# nguyenly.net
KiCad netlist of a schematic drawn in Altium Designer
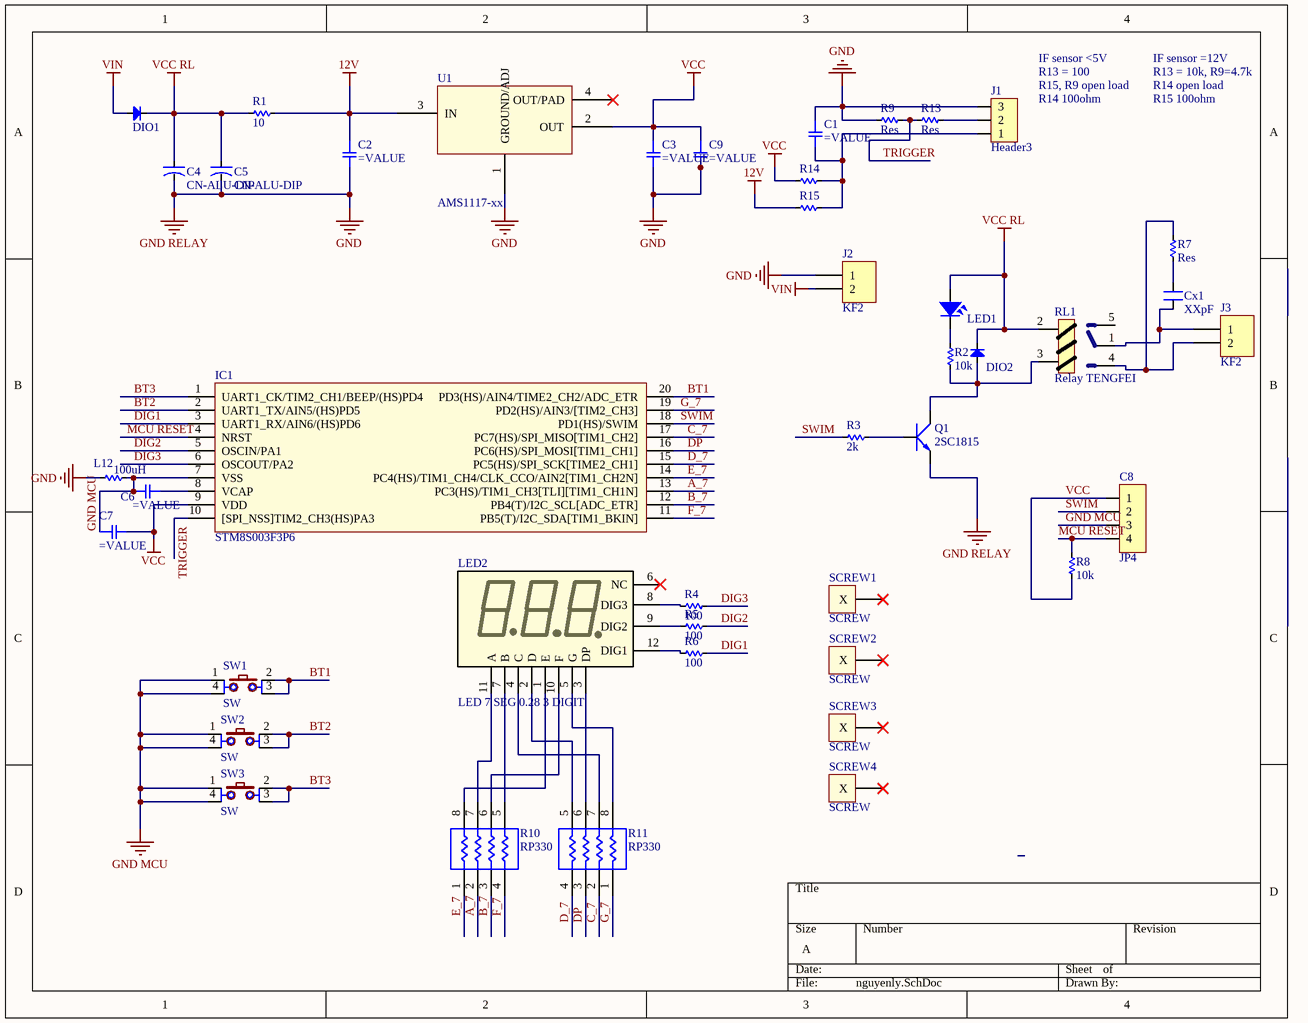
[diagram p0: nguyenly.SchDoc]

(export (version "E")
  (design (tool "Eeschema 10.0.6"))
  (components
    (comp (ref "C1")
      (value "~")
      (footprint "SMD-0805C")
      (description "CAP MLCC SMT")
      (libsource (lib "HOANG_ANH") (part "CAPACITOR"))
    )
    (comp (ref "C2")
      (value "~")
      (footprint "SMD-0805C")
      (description "CAP MLCC SMT")
      (libsource (lib "HOANG_ANH") (part "CAPACITOR"))
    )
    (comp (ref "C3")
      (value "~")
      (footprint "SMD-0805C")
      (description "CAP MLCC SMT")
      (libsource (lib "HOANG_ANH") (part "CAPACITOR"))
    )
    (comp (ref "C4")
      (value "CN-ALU-DIP")
      (footprint "CA-ALU-8")
      (description "Capacitor (Semiconductor SIM Model)")
      (fields (field (name "PUBLISHER") "Altium Limited"))
      (libsource (lib "LIBRARY") (part "CN-ALU-DIP"))
    )
    (comp (ref "C5")
      (value "CN-ALU-DIP")
      (footprint "CA-ALU-8")
      (description "Capacitor (Semiconductor SIM Model)")
      (fields (field (name "PUBLISHER") "Altium Limited"))
      (libsource (lib "LIBRARY") (part "CN-ALU-DIP"))
    )
    (comp (ref "C6")
      (value "~")
      (footprint "SMD-0805C")
      (description "CAP MLCC SMT")
      (libsource (lib "HOANG_ANH") (part "CAPACITOR"))
    )
    (comp (ref "C7")
      (value "~")
      (footprint "SMD-0805C")
      (description "CAP MLCC SMT")
      (libsource (lib "HOANG_ANH") (part "CAPACITOR"))
    )
    (comp (ref "C8")
      (value "JP4")
      (footprint "JP4-C1T")
      (description "WR-PHD 2.54 mm Angled Socket Header")
      (fields
        (field (name "MANUFACTURER") "Würth Elektronik eiSos GmbH")
        (field (name "PARTNO") "613004143121")
        (field (name "CREATED BY") "Karrer Zheng")
      )
      (libsource (lib "LIBRARY") (part "JP4"))
    )
    (comp (ref "C9")
      (value "~")
      (footprint "SMD-0805C")
      (description "CAP MLCC SMT")
      (libsource (lib "HOANG_ANH") (part "CAPACITOR"))
    )
    (comp (ref "Cx1") (value "XXpF") (footprint "CN2.5") (libsource (lib "LIBRARY") (part "CN")))
    (comp (ref "DIO1")
      (value "Diode SMD")
      (footprint "DIO-SMD-106")
      (description "Default Diode")
      (fields (field (name "PUBLISHER") "Altium Limited"))
      (libsource (lib "LIBRARY") (part "Diode SMD"))
    )
    (comp (ref "DIO2")
      (value "Diode SMD")
      (footprint "DIO-SMD-106")
      (description "Default Diode")
      (fields (field (name "PUBLISHER") "Altium Limited"))
      (libsource (lib "LIBRARY") (part "Diode SMD"))
    )
    (comp (ref "IC1")
      (value "STM8S003F3P6")
      (footprint "TSSOP20")
      (description "MCU 8BIT  8KB FLASH TSSOP-20")
      (fields (field (name "COPYRIGHT BY") "VanDungEvn"))
      (libsource (lib "LIBRARY") (part "STM8S003F3P6"))
    )
    (comp (ref "J1")
      (value "Header3")
      (footprint "Header3")
      (description "Header IDC, 3 x 1 Pin Vertical 2.54mm Pitch (Non-Boxed, Male)")
      (fields
        (field (name "MANUFACTURER") "Würth Elektronik eiSos GmbH")
        (field (name "PARTNO") "613002143121")
        (field (name "CREATED BY") "Karrer Zheng")
      )
      (libsource (lib "LIBRARY") (part "Header3"))
    )
    (comp (ref "J2")
      (value "KF2")
      (footprint "KF2-5.08")
      (fields
        (field (name "MANUFACTURER") "Würth Elektronik eiSos GmbH")
        (field (name "PARTNO") "691103110002")
        (field (name "CREATED BY") "Karrer Zheng")
      )
      (libsource (lib "LIBRARY") (part "KF2"))
    )
    (comp (ref "J3")
      (value "KF2")
      (footprint "KF2-5.08")
      (fields
        (field (name "MANUFACTURER") "Würth Elektronik eiSos GmbH")
        (field (name "PARTNO") "691103110002")
        (field (name "CREATED BY") "Karrer Zheng")
      )
      (libsource (lib "LIBRARY") (part "KF2"))
    )
    (comp (ref "L12")
      (value "100uH")
      (footprint "RES-SMD-0805")
      (description "Resistor")
      (fields
        (field (name "MANUFACTURER") "Generic Components")
        (field (name "PUBLISHER") "Altium Hobart Technology Centre")
      )
      (libsource (lib "LIBRARY") (part "Res-SMD"))
    )
    (comp (ref "LED1")
      (value "LED")
      (footprint "LED-0805-Yellow")
      (libsource (lib "LIBRARY") (part "LED SMD"))
    )
    (comp (ref "LED2")
      (value "LED 7 SEG 0.28 3 DIGIT")
      (footprint "LED 7 Seg 0.28, 3 digit, RED")
      (libsource (lib "HOANG_ANH") (part "LED 7 Segment"))
    )
    (comp (ref "Q1")
      (value "2SC1815")
      (footprint "TO92-123")
      (description "NPN 600mW, ECB")
      (libsource (lib "LIBRARY") (part "2SC1815"))
    )
    (comp (ref "R1")
      (value "10")
      (footprint "RES-SMD-0805")
      (description "Resistor")
      (fields
        (field (name "MANUFACTURER") "Generic Components")
        (field (name "PUBLISHER") "Altium Hobart Technology Centre")
      )
      (libsource (lib "LIBRARY") (part "Res-SMD"))
    )
    (comp (ref "R2")
      (value "10k")
      (footprint "RES-SMD-0805")
      (description "Resistor")
      (fields
        (field (name "MANUFACTURER") "Generic Components")
        (field (name "PUBLISHER") "Altium Hobart Technology Centre")
      )
      (libsource (lib "LIBRARY") (part "Res-SMD"))
    )
    (comp (ref "R3")
      (value "2k")
      (footprint "RES-SMD-0805")
      (description "Resistor")
      (fields
        (field (name "MANUFACTURER") "Generic Components")
        (field (name "PUBLISHER") "Altium Hobart Technology Centre")
      )
      (libsource (lib "LIBRARY") (part "Res-SMD"))
    )
    (comp (ref "R4")
      (value "100")
      (footprint "RES-SMD-0805")
      (description "Resistor")
      (fields
        (field (name "MANUFACTURER") "Generic Components")
        (field (name "PUBLISHER") "Altium Hobart Technology Centre")
      )
      (libsource (lib "LIBRARY") (part "Res-SMD"))
    )
    (comp (ref "R5")
      (value "100")
      (footprint "RES-SMD-0805")
      (description "Resistor")
      (fields
        (field (name "MANUFACTURER") "Generic Components")
        (field (name "PUBLISHER") "Altium Hobart Technology Centre")
      )
      (libsource (lib "LIBRARY") (part "Res-SMD"))
    )
    (comp (ref "R6")
      (value "100")
      (footprint "RES-SMD-0805")
      (description "Resistor")
      (fields
        (field (name "MANUFACTURER") "Generic Components")
        (field (name "PUBLISHER") "Altium Hobart Technology Centre")
      )
      (libsource (lib "LIBRARY") (part "Res-SMD"))
    )
    (comp (ref "R7")
      (value "Res")
      (footprint "RES-SMD-0805")
      (description "Resistor")
      (fields
        (field (name "MANUFACTURER") "Generic Components")
        (field (name "PUBLISHER") "Altium Hobart Technology Centre")
      )
      (libsource (lib "LIBRARY") (part "Res-SMD"))
    )
    (comp (ref "R8")
      (value "10k")
      (footprint "RES-SMD-0805")
      (description "Resistor")
      (fields
        (field (name "MANUFACTURER") "Generic Components")
        (field (name "PUBLISHER") "Altium Hobart Technology Centre")
      )
      (libsource (lib "LIBRARY") (part "Res-SMD"))
    )
    (comp (ref "R9")
      (value "Res")
      (footprint "RES-SMD-0805")
      (description "Resistor")
      (fields
        (field (name "MANUFACTURER") "Generic Components")
        (field (name "PUBLISHER") "Altium Hobart Technology Centre")
      )
      (libsource (lib "LIBRARY") (part "Res-SMD"))
    )
    (comp (ref "R10") (value "RP330") (footprint "RN4-0805") (libsource (lib "LIBRARY") (part "RN4-Dual")))
    (comp (ref "R11") (value "RP330") (footprint "RN4-0805") (libsource (lib "LIBRARY") (part "RN4-Dual")))
    (comp (ref "R13")
      (value "Res")
      (footprint "RES-SMD-0805")
      (description "Resistor")
      (fields
        (field (name "MANUFACTURER") "Generic Components")
        (field (name "PUBLISHER") "Altium Hobart Technology Centre")
      )
      (libsource (lib "LIBRARY") (part "Res-SMD"))
    )
    (comp (ref "R14")
      (value "Res")
      (footprint "RES-SMD-0805")
      (description "Resistor")
      (fields
        (field (name "MANUFACTURER") "Generic Components")
        (field (name "PUBLISHER") "Altium Hobart Technology Centre")
      )
      (libsource (lib "LIBRARY") (part "Res-SMD"))
    )
    (comp (ref "R15")
      (value "Res")
      (footprint "RES-SMD-0805")
      (description "Resistor")
      (fields
        (field (name "MANUFACTURER") "Generic Components")
        (field (name "PUBLISHER") "Altium Hobart Technology Centre")
      )
      (libsource (lib "LIBRARY") (part "Res-SMD"))
    )
    (comp (ref "RL1")
      (value "Relay TENGFEI")
      (footprint "JQC-T78-DC12V-A")
      (libsource (lib "HOANG_ANH") (part "Relay TENGFEI"))
    )
    (comp (ref "SCREW1") (value "SCREW") (footprint "SCREW-M5") (libsource (lib "HOANG_ANH") (part "SCREW")))
    (comp (ref "SCREW2") (value "SCREW") (footprint "SCREW-M5") (libsource (lib "HOANG_ANH") (part "SCREW")))
    (comp (ref "SCREW3") (value "SCREW") (footprint "SCREW-M5") (libsource (lib "HOANG_ANH") (part "SCREW")))
    (comp (ref "SCREW4") (value "SCREW") (footprint "SCREW-M5") (libsource (lib "HOANG_ANH") (part "SCREW")))
    (comp (ref "SW1")
      (value "SW")
      (footprint "SW2-DIP")
      (description "Switch button 4 pin")
      (libsource (lib "LIBRARY") (part "SW4"))
    )
    (comp (ref "SW2")
      (value "SW")
      (footprint "SW2-DIP")
      (description "Switch button 4 pin")
      (libsource (lib "LIBRARY") (part "SW4"))
    )
    (comp (ref "SW3")
      (value "SW")
      (footprint "SW2-DIP")
      (description "Switch button 4 pin")
      (libsource (lib "LIBRARY") (part "SW4"))
    )
    (comp (ref "U1")
      (value "AMS1117-xx")
      (footprint "SOT-233")
      (libsource (lib "HOANG_ANH") (part "AMS1117-xx"))
    )
  )
  (nets
    (net (code "1") (name "/A_7") (class "Default")
      (node (ref "IC1") (pin "13") (pinfunction "PC3(HS)/TIM1_CH3[TLI][TIM1_CH1N]_13") (pintype "passive"))
      (node (ref "R10") (pin "2") (pinfunction "2_2") (pintype "passive"))
    )
    (net (code "2") (name "/BT1") (class "Default")
      (node (ref "IC1") (pin "20") (pinfunction "PD3(HS)/AIN4/TIME2_CH2/ADC_ETR_20") (pintype "passive"))
      (node (ref "SW1") (pin "2") (pinfunction "2_2") (pintype "passive"))
      (node (ref "SW1") (pin "3") (pinfunction "3_3") (pintype "passive"))
    )
    (net (code "3") (name "/BT2") (class "Default")
      (node (ref "IC1") (pin "2") (pinfunction "UART1_TX/AIN5/(HS)PD5_2") (pintype "passive"))
      (node (ref "SW2") (pin "2") (pinfunction "2_2") (pintype "passive"))
      (node (ref "SW2") (pin "3") (pinfunction "3_3") (pintype "passive"))
    )
    (net (code "4") (name "/BT3") (class "Default")
      (node (ref "IC1") (pin "1") (pinfunction "UART1_CK/TIM2_CH1/BEEP/(HS)PD4_1") (pintype "passive"))
      (node (ref "SW3") (pin "2") (pinfunction "2_2") (pintype "passive"))
      (node (ref "SW3") (pin "3") (pinfunction "3_3") (pintype "passive"))
    )
    (net (code "5") (name "/B_7") (class "Default")
      (node (ref "IC1") (pin "12") (pinfunction "PB4(T)/I2C_SCL[ADC_ETR]_12") (pintype "passive"))
      (node (ref "R10") (pin "3") (pinfunction "3_3") (pintype "passive"))
    )
    (net (code "6") (name "/C_7") (class "Default")
      (node (ref "IC1") (pin "17") (pinfunction "PC7(HS)/SPI_MISO[TIM1_CH2]_17") (pintype "passive"))
      (node (ref "R11") (pin "2") (pinfunction "2_2") (pintype "passive"))
    )
    (net (code "7") (name "/DIG1") (class "Default")
      (node (ref "IC1") (pin "3") (pinfunction "UART1_RX/AIN6/(HS)PD6_3") (pintype "passive"))
      (node (ref "R6") (pin "1") (pinfunction "1_1") (pintype "passive"))
    )
    (net (code "8") (name "/DIG2") (class "Default")
      (node (ref "IC1") (pin "5") (pinfunction "OSCIN/PA1_5") (pintype "passive"))
      (node (ref "R5") (pin "1") (pinfunction "1_1") (pintype "passive"))
    )
    (net (code "9") (name "/DIG3") (class "Default")
      (node (ref "IC1") (pin "6") (pinfunction "OSCOUT/PA2_6") (pintype "passive"))
      (node (ref "R4") (pin "1") (pinfunction "1_1") (pintype "passive"))
    )
    (net (code "10") (name "/DP") (class "Default")
      (node (ref "IC1") (pin "16") (pinfunction "PC6(HS)/SPI_MOSI[TIM1_CH1]_16") (pintype "passive"))
      (node (ref "R11") (pin "3") (pinfunction "3_3") (pintype "passive"))
    )
    (net (code "11") (name "/D_7") (class "Default")
      (node (ref "IC1") (pin "15") (pinfunction "PC5(HS)/SPI_SCK[TIME2_CH1]_15") (pintype "passive"))
      (node (ref "R11") (pin "4") (pinfunction "4_4") (pintype "passive"))
    )
    (net (code "12") (name "/E_7") (class "Default")
      (node (ref "IC1") (pin "14") (pinfunction "PC4(HS)/TIM1_CH4/CLK_CCO/AIN2[TIM1_CH2N]_14") (pintype "passive"))
      (node (ref "R10") (pin "1") (pinfunction "1_1") (pintype "passive"))
    )
    (net (code "13") (name "/F_7") (class "Default")
      (node (ref "IC1") (pin "11") (pinfunction "PB5(T)/I2C_SDA[TIM1_BKIN]_11") (pintype "passive"))
      (node (ref "R10") (pin "4") (pinfunction "4_4") (pintype "passive"))
    )
    (net (code "14") (name "/G_7") (class "Default")
      (node (ref "IC1") (pin "19") (pinfunction "PD2(HS)/AIN3/[TIM2_CH3]_19") (pintype "passive"))
      (node (ref "R11") (pin "1") (pinfunction "1_1") (pintype "passive"))
    )
    (net (code "15") (name "/MCU RESET") (class "Default")
      (node (ref "C8") (pin "4") (pinfunction "4_4") (pintype "passive"))
      (node (ref "IC1") (pin "4") (pinfunction "NRST_4") (pintype "passive"))
      (node (ref "R8") (pin "2") (pinfunction "2_2") (pintype "passive"))
    )
    (net (code "16") (name "/SWIM") (class "Default")
      (node (ref "C8") (pin "2") (pinfunction "2_2") (pintype "passive"))
      (node (ref "IC1") (pin "18") (pinfunction "PD1(HS)/SWIM_18") (pintype "passive"))
      (node (ref "R3") (pin "2") (pinfunction "2_2") (pintype "passive"))
    )
    (net (code "17") (name "/TRIGGER") (class "Default")
      (node (ref "IC1") (pin "10") (pinfunction "[SPI_NSS]TIM2_CH3(HS)PA3_10") (pintype "passive"))
      (node (ref "R13") (pin "2") (pinfunction "2_2") (pintype "passive"))
      (node (ref "R9") (pin "1") (pinfunction "1_1") (pintype "passive"))
    )
    (net (code "18") (name "12V") (class "Default")
      (node (ref "C2") (pin "1") (pinfunction "1_1") (pintype "passive"))
      (node (ref "R1") (pin "1") (pinfunction "1_1") (pintype "passive"))
      (node (ref "R15") (pin "2") (pinfunction "2_2") (pintype "passive"))
      (node (ref "U1") (pin "3") (pinfunction "IN_3") (pintype "power_in"))
    )
    (net (code "19") (name "GND") (class "Default")
      (node (ref "C1") (pin "1") (pinfunction "1_1") (pintype "passive"))
      (node (ref "C2") (pin "2") (pinfunction "2_2") (pintype "passive"))
      (node (ref "C3") (pin "2") (pinfunction "2_2") (pintype "passive"))
      (node (ref "C4") (pin "2") (pinfunction "2_2") (pintype "passive"))
      (node (ref "C5") (pin "2") (pinfunction "2_2") (pintype "passive"))
      (node (ref "C9") (pin "2") (pinfunction "2_2") (pintype "passive"))
      (node (ref "J1") (pin "3") (pinfunction "3_3") (pintype "passive"))
      (node (ref "J2") (pin "1") (pinfunction "1_1") (pintype "passive"))
      (node (ref "L12") (pin "2") (pinfunction "2_2") (pintype "passive"))
      (node (ref "Q1") (pin "1") (pinfunction "E_1") (pintype "passive"))
      (node (ref "R9") (pin "2") (pinfunction "2_2") (pintype "passive"))
      (node (ref "U1") (pin "1") (pinfunction "GROUND/ADJ_1") (pintype "power_in"))
    )
    (net (code "20") (name "GND MCU") (class "Default")
      (node (ref "C6") (pin "1") (pinfunction "1_1") (pintype "passive"))
      (node (ref "C7") (pin "1") (pinfunction "1_1") (pintype "passive"))
      (node (ref "C8") (pin "3") (pinfunction "3_3") (pintype "passive"))
      (node (ref "IC1") (pin "7") (pinfunction "VSS_7") (pintype "passive"))
      (node (ref "L12") (pin "1") (pinfunction "1_1") (pintype "passive"))
      (node (ref "SW1") (pin "1") (pintype "passive"))
      (node (ref "SW1") (pin "4") (pinfunction "4_4") (pintype "passive"))
      (node (ref "SW2") (pin "1") (pintype "passive"))
      (node (ref "SW2") (pin "4") (pinfunction "4_4") (pintype "passive"))
      (node (ref "SW3") (pin "1") (pintype "passive"))
      (node (ref "SW3") (pin "4") (pinfunction "4_4") (pintype "passive"))
    )
    (net (code "21") (name "Net-(C1-Pad2)") (class "Default")
      (node (ref "C1") (pin "2") (pinfunction "2_2") (pintype "passive"))
      (node (ref "J1") (pin "1") (pinfunction "1_1") (pintype "passive"))
      (node (ref "R14") (pin "1") (pinfunction "1_1") (pintype "passive"))
      (node (ref "R15") (pin "1") (pinfunction "1_1") (pintype "passive"))
    )
    (net (code "22") (name "Net-(Cx1-Pad1)") (class "Default")
      (node (ref "Cx1") (pin "1") (pinfunction "1_1") (pintype "passive"))
      (node (ref "R7") (pin "2") (pinfunction "2_2") (pintype "passive"))
    )
    (net (code "23") (name "Net-(Cx1-Pad2)") (class "Default")
      (node (ref "Cx1") (pin "2") (pinfunction "2_2") (pintype "passive"))
      (node (ref "J3") (pin "1") (pinfunction "1_1") (pintype "passive"))
      (node (ref "RL1") (pin "1") (pinfunction "1_1") (pintype "passive"))
    )
    (net (code "24") (name "Net-(DIO2-A)") (class "Default")
      (node (ref "DIO2") (pin "1") (pinfunction "A_1") (pintype "passive"))
      (node (ref "Q1") (pin "2") (pinfunction "C_2") (pintype "passive"))
      (node (ref "R2") (pin "2") (pinfunction "2_2") (pintype "passive"))
      (node (ref "RL1") (pin "3") (pinfunction "3_3") (pintype "passive"))
    )
    (net (code "25") (name "Net-(IC1-VCAP)") (class "Default")
      (node (ref "C6") (pin "2") (pinfunction "2_2") (pintype "passive"))
      (node (ref "IC1") (pin "8") (pinfunction "VCAP_8") (pintype "passive"))
    )
    (net (code "26") (name "Net-(J1-Pad2)") (class "Default")
      (node (ref "J1") (pin "2") (pinfunction "2_2") (pintype "passive"))
      (node (ref "R13") (pin "1") (pinfunction "1_1") (pintype "passive"))
    )
    (net (code "27") (name "Net-(J3-Pad2)") (class "Default")
      (node (ref "J3") (pin "2") (pinfunction "2_2") (pintype "passive"))
      (node (ref "R7") (pin "1") (pinfunction "1_1") (pintype "passive"))
      (node (ref "RL1") (pin "4") (pinfunction "4_4") (pintype "passive"))
    )
    (net (code "28") (name "Net-(LED1-Pad2)") (class "Default")
      (node (ref "LED1") (pin "2") (pinfunction "2_2") (pintype "passive"))
      (node (ref "R2") (pin "1") (pinfunction "1_1") (pintype "passive"))
    )
    (net (code "29") (name "Net-(LED2-A)") (class "Default")
      (node (ref "LED2") (pin "11") (pinfunction "A_11") (pintype "passive"))
      (node (ref "R10") (pin "7") (pinfunction "7_7") (pintype "passive"))
    )
    (net (code "30") (name "Net-(LED2-B)") (class "Default")
      (node (ref "LED2") (pin "7") (pinfunction "B_7") (pintype "passive"))
      (node (ref "R10") (pin "5") (pinfunction "5_5") (pintype "passive"))
    )
    (net (code "31") (name "Net-(LED2-C)") (class "Default")
      (node (ref "LED2") (pin "4") (pinfunction "C_4") (pintype "passive"))
      (node (ref "R11") (pin "7") (pinfunction "7_7") (pintype "passive"))
    )
    (net (code "32") (name "Net-(LED2-D)") (class "Default")
      (node (ref "LED2") (pin "2") (pinfunction "D_2") (pintype "passive"))
      (node (ref "R11") (pin "5") (pinfunction "5_5") (pintype "passive"))
    )
    (net (code "33") (name "Net-(LED2-DIG1)") (class "Default")
      (node (ref "LED2") (pin "12") (pinfunction "DIG1_12") (pintype "passive"))
      (node (ref "R6") (pin "2") (pinfunction "2_2") (pintype "passive"))
    )
    (net (code "34") (name "Net-(LED2-DIG2)") (class "Default")
      (node (ref "LED2") (pin "9") (pinfunction "DIG2_9") (pintype "passive"))
      (node (ref "R5") (pin "2") (pinfunction "2_2") (pintype "passive"))
    )
    (net (code "35") (name "Net-(LED2-DIG3)") (class "Default")
      (node (ref "LED2") (pin "8") (pinfunction "DIG3_8") (pintype "passive"))
      (node (ref "R4") (pin "2") (pinfunction "2_2") (pintype "passive"))
    )
    (net (code "36") (name "Net-(LED2-DP)") (class "Default")
      (node (ref "LED2") (pin "3") (pinfunction "DP_3") (pintype "passive"))
      (node (ref "R11") (pin "6") (pinfunction "6_6") (pintype "passive"))
    )
    (net (code "37") (name "Net-(LED2-E)") (class "Default")
      (node (ref "LED2") (pin "1") (pinfunction "E_1") (pintype "passive"))
      (node (ref "R10") (pin "8") (pinfunction "8_8") (pintype "passive"))
    )
    (net (code "38") (name "Net-(LED2-F)") (class "Default")
      (node (ref "LED2") (pin "10") (pinfunction "F_10") (pintype "passive"))
      (node (ref "R10") (pin "6") (pinfunction "6_6") (pintype "passive"))
    )
    (net (code "39") (name "Net-(LED2-G)") (class "Default")
      (node (ref "LED2") (pin "5") (pinfunction "G_5") (pintype "passive"))
      (node (ref "R11") (pin "8") (pinfunction "8_8") (pintype "passive"))
    )
    (net (code "40") (name "Net-(Q1-B)") (class "Default")
      (node (ref "Q1") (pin "3") (pinfunction "B_3") (pintype "passive"))
      (node (ref "R3") (pin "1") (pinfunction "1_1") (pintype "passive"))
    )
    (net (code "41") (name "VCC") (class "Default")
      (node (ref "C3") (pin "1") (pinfunction "1_1") (pintype "passive"))
      (node (ref "C7") (pin "2") (pinfunction "2_2") (pintype "passive"))
      (node (ref "C8") (pin "1") (pinfunction "1_1") (pintype "passive"))
      (node (ref "C9") (pin "1") (pinfunction "1_1") (pintype "passive"))
      (node (ref "IC1") (pin "9") (pinfunction "VDD_9") (pintype "passive"))
      (node (ref "R14") (pin "2") (pinfunction "2_2") (pintype "passive"))
      (node (ref "R8") (pin "1") (pinfunction "1_1") (pintype "passive"))
      (node (ref "U1") (pin "2") (pinfunction "OUT_2") (pintype "power_in"))
    )
    (net (code "42") (name "VCC RL") (class "Default")
      (node (ref "C4") (pin "1") (pinfunction "1_1") (pintype "passive"))
      (node (ref "C5") (pin "1") (pinfunction "1_1") (pintype "passive"))
      (node (ref "DIO1") (pin "2") (pinfunction "K_2") (pintype "passive"))
      (node (ref "DIO2") (pin "2") (pinfunction "K_2") (pintype "passive"))
      (node (ref "LED1") (pin "1") (pinfunction "1_1") (pintype "passive"))
      (node (ref "R1") (pin "2") (pinfunction "2_2") (pintype "passive"))
      (node (ref "RL1") (pin "2") (pinfunction "2_2") (pintype "passive"))
    )
    (net (code "43") (name "VIN") (class "Default")
      (node (ref "DIO1") (pin "1") (pinfunction "A_1") (pintype "passive"))
      (node (ref "J2") (pin "2") (pinfunction "2_2") (pintype "passive"))
    )
    (net (code "44") (name "unconnected-(LED2-NC-Pad6)") (class "Default")
      (node (ref "LED2") (pin "6") (pinfunction "NC_6") (pintype "passive+no_connect"))
    )
    (net (code "45") (name "unconnected-(RL1-Pad5)") (class "Default")
      (node (ref "RL1") (pin "5") (pinfunction "5_5") (pintype "passive"))
    )
    (net (code "46") (name "unconnected-(SCREW1-X-Pad1)") (class "Default")
      (node (ref "SCREW1") (pin "1") (pinfunction "X_1") (pintype "passive+no_connect"))
    )
    (net (code "47") (name "unconnected-(SCREW2-X-Pad1)") (class "Default")
      (node (ref "SCREW2") (pin "1") (pinfunction "X_1") (pintype "passive+no_connect"))
    )
    (net (code "48") (name "unconnected-(SCREW3-X-Pad1)") (class "Default")
      (node (ref "SCREW3") (pin "1") (pinfunction "X_1") (pintype "passive+no_connect"))
    )
    (net (code "49") (name "unconnected-(SCREW4-X-Pad1)") (class "Default")
      (node (ref "SCREW4") (pin "1") (pinfunction "X_1") (pintype "passive+no_connect"))
    )
    (net (code "50") (name "unconnected-(U1-OUT{slash}PAD-Pad4)") (class "Default")
      (node (ref "U1") (pin "4") (pinfunction "OUT/PAD_4") (pintype "power_in+no_connect"))
    )
  )
)
